# Si1132_breakout.net
KiCad netlist of a schematic drawn in EAGLE
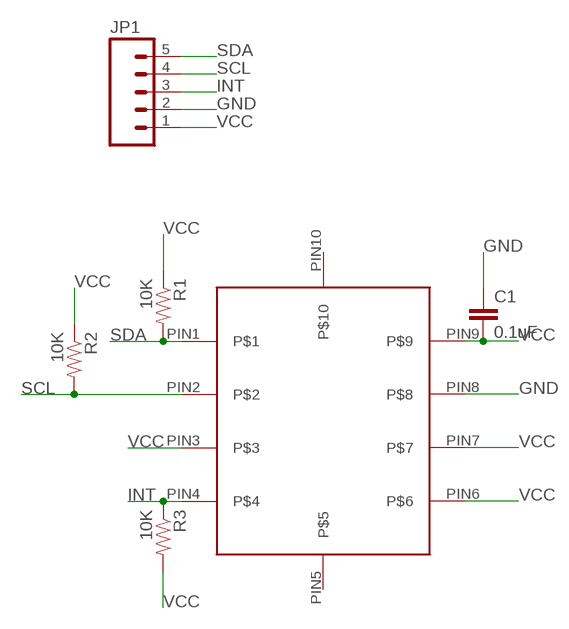
[diagram p0: schematic, sheet 1]

(export (version "E")
  (design (tool "Eeschema 10.0.6"))
  (components
    (comp (ref "C1")
      (value "0.1uF")
      (footprint "eagle-import:0603-CAP")
      (libsource (lib "eagle-import") (part "CAP0603-CAP"))
    )
    (comp (ref "JP1")
      (value "M05PTH")
      (footprint "eagle-import:1X05")
      (libsource (lib "eagle-import") (part "M05PTH"))
    )
    (comp (ref "R1")
      (value "10K")
      (footprint "eagle-import:0603-RES")
      (libsource (lib "eagle-import") (part "RESISTOR0603"))
    )
    (comp (ref "R2")
      (value "10K")
      (footprint "eagle-import:0603-RES")
      (libsource (lib "eagle-import") (part "RESISTOR0603"))
    )
    (comp (ref "R3")
      (value "10K")
      (footprint "eagle-import:0603-RES")
      (libsource (lib "eagle-import") (part "RESISTOR0603"))
    )
    (comp (ref "U$1")
      (value "SI1132")
      (footprint "eagle-import:SI1132")
      (libsource (lib "eagle-import") (part "SI1132"))
    )
  )
  (nets
    (net (code "1") (name "/GND") (class "Default")
      (node (ref "C1") (pin "1") (pinfunction "1_1") (pintype "passive"))
      (node (ref "JP1") (pin "2") (pinfunction "2_2") (pintype "passive"))
      (node (ref "U$1") (pin "PIN8") (pinfunction "P$8_PIN8") (pintype "bidirectional"))
    )
    (net (code "2") (name "/INT") (class "Default")
      (node (ref "JP1") (pin "3") (pinfunction "3_3") (pintype "passive"))
      (node (ref "R3") (pin "1") (pinfunction "1_1") (pintype "passive"))
      (node (ref "U$1") (pin "PIN4") (pinfunction "P$4_PIN4") (pintype "bidirectional"))
    )
    (net (code "3") (name "/SCL") (class "Default")
      (node (ref "JP1") (pin "4") (pinfunction "4_4") (pintype "passive"))
      (node (ref "R2") (pin "2") (pinfunction "2_2") (pintype "passive"))
      (node (ref "U$1") (pin "PIN2") (pinfunction "P$2_PIN2") (pintype "bidirectional"))
    )
    (net (code "4") (name "/SDA") (class "Default")
      (node (ref "JP1") (pin "5") (pinfunction "5_5") (pintype "passive"))
      (node (ref "R1") (pin "2") (pinfunction "2_2") (pintype "passive"))
      (node (ref "U$1") (pin "PIN1") (pinfunction "P$1_PIN1") (pintype "bidirectional"))
    )
    (net (code "5") (name "/VCC") (class "Default")
      (node (ref "C1") (pin "2") (pinfunction "2_2") (pintype "passive"))
      (node (ref "JP1") (pin "1") (pinfunction "1_1") (pintype "passive"))
      (node (ref "R1") (pin "1") (pinfunction "1_1") (pintype "passive"))
      (node (ref "R2") (pin "1") (pinfunction "1_1") (pintype "passive"))
      (node (ref "R3") (pin "2") (pinfunction "2_2") (pintype "passive"))
      (node (ref "U$1") (pin "PIN3") (pinfunction "P$3_PIN3") (pintype "bidirectional"))
      (node (ref "U$1") (pin "PIN6") (pinfunction "P$6_PIN6") (pintype "bidirectional"))
      (node (ref "U$1") (pin "PIN7") (pinfunction "P$7_PIN7") (pintype "bidirectional"))
      (node (ref "U$1") (pin "PIN9") (pinfunction "P$9_PIN9") (pintype "bidirectional"))
    )
    (net (code "6") (name "unconnected-(U$1-P$5-PadPIN5)") (class "Default")
      (node (ref "U$1") (pin "PIN5") (pinfunction "P$5_PIN5") (pintype "bidirectional"))
    )
    (net (code "7") (name "unconnected-(U$1-P$10-PadPIN10)") (class "Default")
      (node (ref "U$1") (pin "PIN10") (pinfunction "P$10_PIN10") (pintype "bidirectional"))
    )
  )
)
